# sandbox_main_v2e.net
KiCad netlist of a schematic drawn in EAGLE
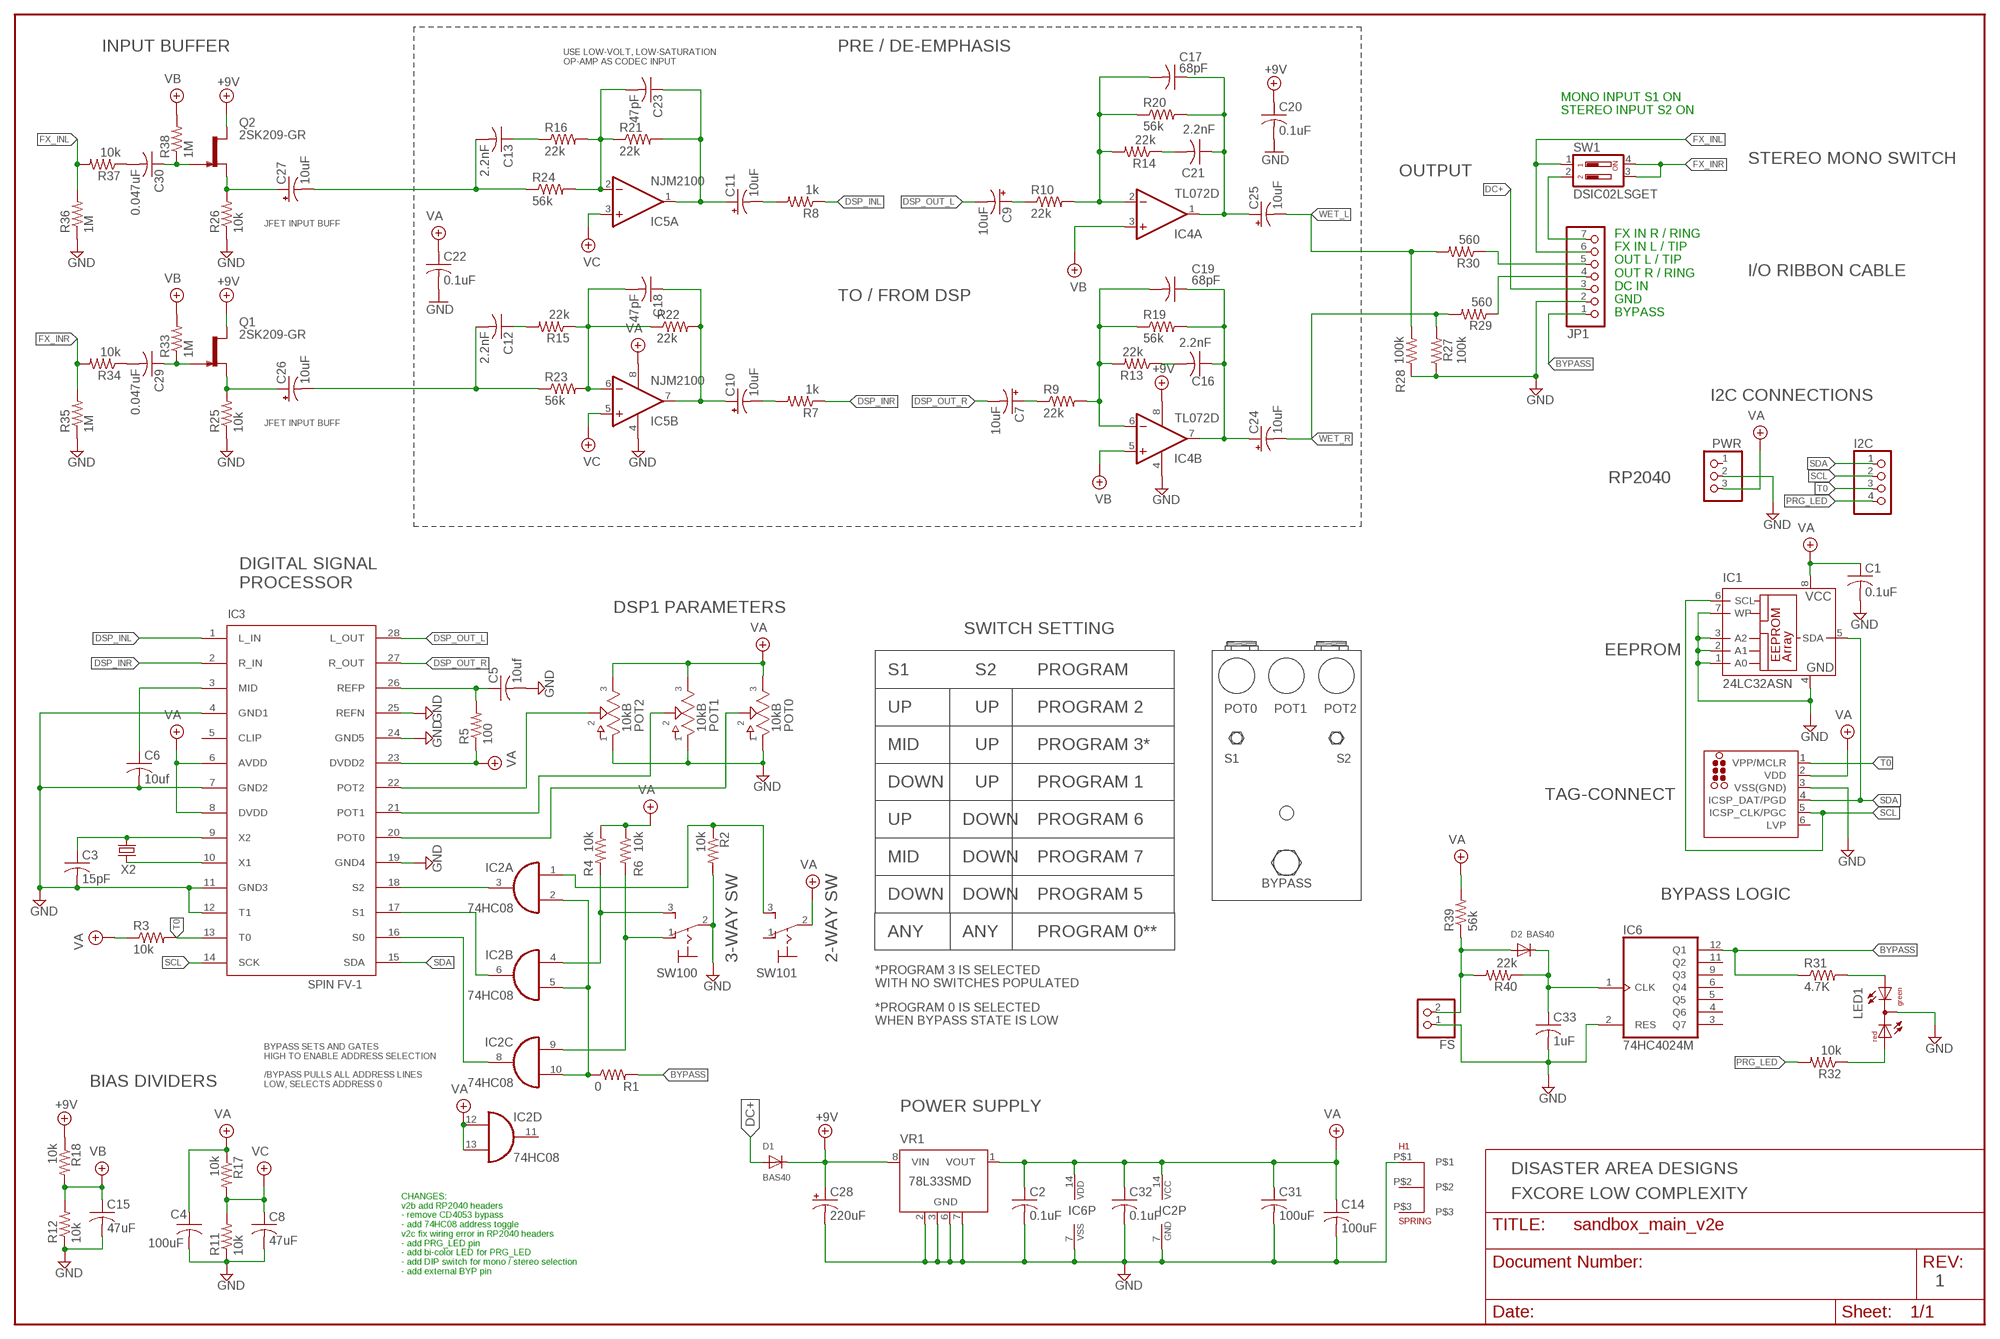
[diagram p0: schematic, sheet 1]

(export (version "E")
  (design (tool "Eeschema 10.0.6"))
  (components
    (comp (ref "C1")
      (value "0.1uF")
      (footprint "eagle-import:C0805K")
      (libsource (lib "eagle-import") (part "C-USC0805K"))
    )
    (comp (ref "C2")
      (value "0.1uF")
      (footprint "eagle-import:C0805K")
      (libsource (lib "eagle-import") (part "C-USC0805K"))
    )
    (comp (ref "C3")
      (value "15pF")
      (footprint "eagle-import:C0805K")
      (libsource (lib "eagle-import") (part "C-USC0805K"))
    )
    (comp (ref "C4")
      (value "100uF")
      (footprint "eagle-import:C1206K")
      (libsource (lib "eagle-import") (part "C-USC1206K"))
    )
    (comp (ref "C5")
      (value "10uf")
      (footprint "eagle-import:C0805K")
      (libsource (lib "eagle-import") (part "C-USC0805K"))
    )
    (comp (ref "C6")
      (value "10uf")
      (footprint "eagle-import:C0805K")
      (libsource (lib "eagle-import") (part "C-USC0805K"))
    )
    (comp (ref "C7")
      (value "10uF")
      (footprint "eagle-import:CT3216")
      (libsource (lib "eagle-import") (part "CPOL-USCT3216"))
    )
    (comp (ref "C8")
      (value "47uF")
      (footprint "eagle-import:C1206K")
      (libsource (lib "eagle-import") (part "C-USC1206K"))
    )
    (comp (ref "C9")
      (value "10uF")
      (footprint "eagle-import:CT3216")
      (libsource (lib "eagle-import") (part "CPOL-USCT3216"))
    )
    (comp (ref "C10")
      (value "10uF")
      (footprint "eagle-import:CT3216")
      (libsource (lib "eagle-import") (part "CPOL-USCT3216"))
    )
    (comp (ref "C11")
      (value "10uF")
      (footprint "eagle-import:CT3216")
      (libsource (lib "eagle-import") (part "CPOL-USCT3216"))
    )
    (comp (ref "C12")
      (value "2.2nF")
      (footprint "eagle-import:C0805K")
      (libsource (lib "eagle-import") (part "C-USC0805K"))
    )
    (comp (ref "C13")
      (value "2.2nF")
      (footprint "eagle-import:C0805K")
      (libsource (lib "eagle-import") (part "C-USC0805K"))
    )
    (comp (ref "C14")
      (value "100uF")
      (footprint "eagle-import:C1206K")
      (libsource (lib "eagle-import") (part "C-USC1206K"))
    )
    (comp (ref "C15")
      (value "47uF")
      (footprint "eagle-import:C1206K")
      (libsource (lib "eagle-import") (part "C-USC1206K"))
    )
    (comp (ref "C16")
      (value "2.2nF")
      (footprint "eagle-import:C0805K")
      (libsource (lib "eagle-import") (part "C-USC0805K"))
    )
    (comp (ref "C17")
      (value "68pF")
      (footprint "eagle-import:C0805K")
      (libsource (lib "eagle-import") (part "C-USC0805K"))
    )
    (comp (ref "C18")
      (value "47pF")
      (footprint "eagle-import:C0805K")
      (libsource (lib "eagle-import") (part "C-USC0805K"))
    )
    (comp (ref "C19")
      (value "68pF")
      (footprint "eagle-import:C0805K")
      (libsource (lib "eagle-import") (part "C-USC0805K"))
    )
    (comp (ref "C20")
      (value "0.1uF")
      (footprint "eagle-import:C0805K")
      (libsource (lib "eagle-import") (part "C-USC0805K"))
    )
    (comp (ref "C21")
      (value "2.2nF")
      (footprint "eagle-import:C0805K")
      (libsource (lib "eagle-import") (part "C-USC0805K"))
    )
    (comp (ref "C22")
      (value "0.1uF")
      (footprint "eagle-import:C0805K")
      (libsource (lib "eagle-import") (part "C-USC0805K"))
    )
    (comp (ref "C23")
      (value "47pF")
      (footprint "eagle-import:C0805K")
      (libsource (lib "eagle-import") (part "C-USC0805K"))
    )
    (comp (ref "C24")
      (value "10uF")
      (footprint "eagle-import:CT3216")
      (libsource (lib "eagle-import") (part "CPOL-USCT3216"))
    )
    (comp (ref "C25")
      (value "10uF")
      (footprint "eagle-import:CT3216")
      (libsource (lib "eagle-import") (part "CPOL-USCT3216"))
    )
    (comp (ref "C26")
      (value "10uF")
      (footprint "eagle-import:CT3216")
      (libsource (lib "eagle-import") (part "CPOL-USCT3216"))
    )
    (comp (ref "C27")
      (value "10uF")
      (footprint "eagle-import:CT3216")
      (libsource (lib "eagle-import") (part "CPOL-USCT3216"))
    )
    (comp (ref "C28")
      (value "220uF")
      (footprint "eagle-import:PANASONIC_D")
      (libsource (lib "eagle-import") (part "CPOL-USD"))
    )
    (comp (ref "C29")
      (value "0.047uF")
      (footprint "eagle-import:C1206K")
      (libsource (lib "eagle-import") (part "C-USC1206K"))
    )
    (comp (ref "C30")
      (value "0.047uF")
      (footprint "eagle-import:C1206K")
      (libsource (lib "eagle-import") (part "C-USC1206K"))
    )
    (comp (ref "C31")
      (value "100uF")
      (footprint "eagle-import:C1206K")
      (libsource (lib "eagle-import") (part "C-USC1206K"))
    )
    (comp (ref "C32")
      (value "0.1uF")
      (footprint "eagle-import:C0805K")
      (libsource (lib "eagle-import") (part "C-USC0805K"))
    )
    (comp (ref "C33")
      (value "1uF")
      (footprint "eagle-import:C0805K")
      (libsource (lib "eagle-import") (part "C-USC0805K"))
    )
    (comp (ref "D1")
      (value "BAS40")
      (footprint "eagle-import:SOT23-R")
      (libsource (lib "eagle-import") (part "DIODESOT23_REFLOW"))
    )
    (comp (ref "D2")
      (value "BAS40")
      (footprint "eagle-import:SOT23-R")
      (libsource (lib "eagle-import") (part "DIODESOT23_REFLOW"))
    )
    (comp (ref "FS")
      (value "PINHD-1X2")
      (footprint "eagle-import:1X02")
      (libsource (lib "eagle-import") (part "PINHD-1X2"))
    )
    (comp (ref "H1")
      (value "628")
      (footprint "eagle-import:628")
      (libsource (lib "eagle-import") (part "628"))
    )
    (comp (ref "I2C")
      (value "PINHD-1X4")
      (footprint "eagle-import:1X04")
      (libsource (lib "eagle-import") (part "PINHD-1X4"))
    )
    (comp (ref "IC1")
      (value "24LC32ASN")
      (footprint "eagle-import:SO-08")
      (fields (field (name "MF") "MICROCHIP") (field (name "MPN") "24LC32A/SN"))
      (libsource (lib "eagle-import") (part "24SNLC32A"))
    )
    (comp (ref "IC2")
      (value "74HC08")
      (footprint "eagle-import:SO14")
      (libsource (lib "eagle-import") (part "7408DAC"))
    )
    (comp (ref "IC3")
      (value "SPINFV-1")
      (footprint "eagle-import:SOIC-28")
      (libsource (lib "eagle-import") (part "SPINFV-1"))
    )
    (comp (ref "IC4")
      (value "TL072D")
      (footprint "eagle-import:SO08")
      (libsource (lib "eagle-import") (part "TL072D"))
    )
    (comp (ref "IC5")
      (value "NJM2100")
      (footprint "eagle-import:SO08")
      (libsource (lib "eagle-import") (part "TL072D"))
    )
    (comp (ref "IC6")
      (value "74HC4024M")
      (footprint "eagle-import:SO14")
      (libsource (lib "eagle-import") (part "4024D"))
    )
    (comp (ref "JP1")
      (value "PINHD-1X7")
      (footprint "eagle-import:1X07")
      (libsource (lib "eagle-import") (part "PINHD-1X7"))
    )
    (comp (ref "LED1")
      (value "DUOLED-RG-C")
      (footprint "eagle-import:DUOLED-C-5MM")
      (libsource (lib "eagle-import") (part "DUOLED-RG-C"))
    )
    (comp (ref "POT0")
      (value "10kB")
      (footprint "eagle-import:POT_9MM_PACK_SM")
      (libsource (lib "eagle-import") (part "POT_9MM_317-2080F_SM"))
    )
    (comp (ref "POT1")
      (value "10kB")
      (footprint "eagle-import:POT_9MM_PACK_SM")
      (libsource (lib "eagle-import") (part "POT_9MM_317-2080F_SM"))
    )
    (comp (ref "POT2")
      (value "10kB")
      (footprint "eagle-import:POT_9MM_PACK_SM")
      (libsource (lib "eagle-import") (part "POT_9MM_317-2080F_SM"))
    )
    (comp (ref "PWR")
      (value "PINHD-1X3")
      (footprint "eagle-import:1X03")
      (libsource (lib "eagle-import") (part "PINHD-1X3"))
    )
    (comp (ref "Q1")
      (value "2SK209-GR")
      (footprint "eagle-import:SOT-23")
      (libsource (lib "eagle-import") (part "2N5457SMT"))
    )
    (comp (ref "Q2")
      (value "2SK209-GR")
      (footprint "eagle-import:SOT-23")
      (libsource (lib "eagle-import") (part "2N5457SMT"))
    )
    (comp (ref "R1")
      (value "0")
      (footprint "eagle-import:R0805")
      (libsource (lib "eagle-import") (part "R-US_R0805"))
    )
    (comp (ref "R2")
      (value "10k")
      (footprint "eagle-import:R0805")
      (libsource (lib "eagle-import") (part "R-US_R0805"))
    )
    (comp (ref "R3")
      (value "10k")
      (footprint "eagle-import:R0805")
      (libsource (lib "eagle-import") (part "R-US_R0805"))
    )
    (comp (ref "R4")
      (value "10k")
      (footprint "eagle-import:R0805")
      (libsource (lib "eagle-import") (part "R-US_R0805"))
    )
    (comp (ref "R5")
      (value "100")
      (footprint "eagle-import:R0805")
      (libsource (lib "eagle-import") (part "R-US_R0805"))
    )
    (comp (ref "R6")
      (value "10k")
      (footprint "eagle-import:R0805")
      (libsource (lib "eagle-import") (part "R-US_R0805"))
    )
    (comp (ref "R7")
      (value "1k")
      (footprint "eagle-import:R0805")
      (libsource (lib "eagle-import") (part "R-US_R0805"))
    )
    (comp (ref "R8")
      (value "1k")
      (footprint "eagle-import:R0805")
      (libsource (lib "eagle-import") (part "R-US_R0805"))
    )
    (comp (ref "R9")
      (value "22k")
      (footprint "eagle-import:R0805")
      (libsource (lib "eagle-import") (part "R-US_R0805"))
    )
    (comp (ref "R10")
      (value "22k")
      (footprint "eagle-import:R0805")
      (libsource (lib "eagle-import") (part "R-US_R0805"))
    )
    (comp (ref "R11")
      (value "10k")
      (footprint "eagle-import:R0805")
      (libsource (lib "eagle-import") (part "R-US_R0805"))
    )
    (comp (ref "R12")
      (value "10k")
      (footprint "eagle-import:R0805")
      (libsource (lib "eagle-import") (part "R-US_R0805"))
    )
    (comp (ref "R13")
      (value "22k")
      (footprint "eagle-import:R0805")
      (libsource (lib "eagle-import") (part "R-US_R0805"))
    )
    (comp (ref "R14")
      (value "22k")
      (footprint "eagle-import:R0805")
      (libsource (lib "eagle-import") (part "R-US_R0805"))
    )
    (comp (ref "R15")
      (value "22k")
      (footprint "eagle-import:R0805")
      (libsource (lib "eagle-import") (part "R-US_R0805"))
    )
    (comp (ref "R16")
      (value "22k")
      (footprint "eagle-import:R0805")
      (libsource (lib "eagle-import") (part "R-US_R0805"))
    )
    (comp (ref "R17")
      (value "10k")
      (footprint "eagle-import:R0805")
      (libsource (lib "eagle-import") (part "R-US_R0805"))
    )
    (comp (ref "R18")
      (value "10k")
      (footprint "eagle-import:R0805")
      (libsource (lib "eagle-import") (part "R-US_R0805"))
    )
    (comp (ref "R19")
      (value "56k")
      (footprint "eagle-import:R0805")
      (libsource (lib "eagle-import") (part "R-US_R0805"))
    )
    (comp (ref "R20")
      (value "56k")
      (footprint "eagle-import:R0805")
      (libsource (lib "eagle-import") (part "R-US_R0805"))
    )
    (comp (ref "R21")
      (value "22k")
      (footprint "eagle-import:R0805")
      (libsource (lib "eagle-import") (part "R-US_R0805"))
    )
    (comp (ref "R22")
      (value "22k")
      (footprint "eagle-import:R0805")
      (libsource (lib "eagle-import") (part "R-US_R0805"))
    )
    (comp (ref "R23")
      (value "56k")
      (footprint "eagle-import:R0805")
      (libsource (lib "eagle-import") (part "R-US_R0805"))
    )
    (comp (ref "R24")
      (value "56k")
      (footprint "eagle-import:R0805")
      (libsource (lib "eagle-import") (part "R-US_R0805"))
    )
    (comp (ref "R25")
      (value "10k")
      (footprint "eagle-import:R0805")
      (libsource (lib "eagle-import") (part "R-US_R0805"))
    )
    (comp (ref "R26")
      (value "10k")
      (footprint "eagle-import:R0805")
      (libsource (lib "eagle-import") (part "R-US_R0805"))
    )
    (comp (ref "R27")
      (value "100k")
      (footprint "eagle-import:R0805")
      (libsource (lib "eagle-import") (part "R-US_R0805"))
    )
    (comp (ref "R28")
      (value "100k")
      (footprint "eagle-import:R0805")
      (libsource (lib "eagle-import") (part "R-US_R0805"))
    )
    (comp (ref "R29")
      (value "560")
      (footprint "eagle-import:R0805")
      (libsource (lib "eagle-import") (part "R-US_R0805"))
    )
    (comp (ref "R30")
      (value "560")
      (footprint "eagle-import:R0805")
      (libsource (lib "eagle-import") (part "R-US_R0805"))
    )
    (comp (ref "R31")
      (value "4.7K")
      (footprint "eagle-import:R0805")
      (libsource (lib "eagle-import") (part "R-US_R0805"))
    )
    (comp (ref "R32")
      (value "10k")
      (footprint "eagle-import:R0805")
      (libsource (lib "eagle-import") (part "R-US_R0805"))
    )
    (comp (ref "R33")
      (value "1M")
      (footprint "eagle-import:R0805")
      (libsource (lib "eagle-import") (part "R-US_R0805"))
    )
    (comp (ref "R34")
      (value "10k")
      (footprint "eagle-import:R0805")
      (libsource (lib "eagle-import") (part "R-US_R0805"))
    )
    (comp (ref "R35")
      (value "1M")
      (footprint "eagle-import:R0805")
      (libsource (lib "eagle-import") (part "R-US_R0805"))
    )
    (comp (ref "R36")
      (value "1M")
      (footprint "eagle-import:R0805")
      (libsource (lib "eagle-import") (part "R-US_R0805"))
    )
    (comp (ref "R37")
      (value "10k")
      (footprint "eagle-import:R0805")
      (libsource (lib "eagle-import") (part "R-US_R0805"))
    )
    (comp (ref "R38")
      (value "1M")
      (footprint "eagle-import:R0805")
      (libsource (lib "eagle-import") (part "R-US_R0805"))
    )
    (comp (ref "R39")
      (value "56k")
      (footprint "eagle-import:R0805")
      (libsource (lib "eagle-import") (part "R-US_R0805"))
    )
    (comp (ref "R40")
      (value "22k")
      (footprint "eagle-import:R0805")
      (libsource (lib "eagle-import") (part "R-US_R0805"))
    )
    (comp (ref "SW1")
      (value "DSIC02LSGET")
      (footprint "eagle-import:CTS-219-02")
      (libsource (lib "eagle-import") (part "219-02"))
    )
    (comp (ref "SW100")
      (value "320-916")
      (footprint "eagle-import:320-916")
      (libsource (lib "eagle-import") (part "320-916"))
    )
    (comp (ref "SW101")
      (value "320-916")
      (footprint "eagle-import:320-916")
      (libsource (lib "eagle-import") (part "320-916"))
    )
    (comp (ref "TC1")
      (value "TC2030_ICSP-MCP-NL")
      (footprint "eagle-import:TC2030-MCP-NL")
      (libsource (lib "eagle-import") (part "TC2030_ICSP-MCP-NL"))
    )
    (comp (ref "VR1")
      (value "78L33SMD")
      (footprint "eagle-import:SO08")
      (libsource (lib "eagle-import") (part "78LSMD05"))
    )
    (comp (ref "X2")
      (value "32.768kHz")
      (footprint "eagle-import:CRYSTAL-SMD-3.2X1.5MM")
      (libsource (lib "eagle-import") (part "CRYSTAL3.2X1.5MM"))
    )
  )
  (nets
    (net (code "1") (name "+9V") (class "Default")
      (node (ref "C20") (pin "1") (pinfunction "1_1") (pintype "passive"))
      (node (ref "C28") (pin "+") (pinfunction "+_+") (pintype "passive"))
      (node (ref "D1") (pin "3") (pinfunction "C_3") (pintype "passive"))
      (node (ref "IC4") (pin "8") (pinfunction "V+_8") (pintype "power_in"))
      (node (ref "Q1") (pin "2") (pinfunction "D_2") (pintype "passive"))
      (node (ref "Q2") (pin "2") (pinfunction "D_2") (pintype "passive"))
      (node (ref "R18") (pin "1") (pinfunction "1_1") (pintype "passive"))
      (node (ref "VR1") (pin "8") (pinfunction "VIN_8") (pintype "passive"))
    )
    (net (code "2") (name "BYPASS") (class "Default")
      (node (ref "IC6") (pin "12") (pinfunction "Q1_12") (pintype "output"))
      (node (ref "JP1") (pin "1") (pinfunction "1_1") (pintype "passive"))
      (node (ref "R1") (pin "2") (pinfunction "2_2") (pintype "passive"))
      (node (ref "R31") (pin "1") (pinfunction "1_1") (pintype "passive"))
    )
    (net (code "3") (name "DC+") (class "Default")
      (node (ref "D1") (pin "1") (pinfunction "A_1") (pintype "passive"))
      (node (ref "JP1") (pin "3") (pinfunction "3_3") (pintype "passive"))
    )
    (net (code "4") (name "DSP_INL") (class "Default")
      (node (ref "IC3") (pin "1") (pinfunction "L_IN_1") (pintype "bidirectional"))
      (node (ref "R8") (pin "1") (pinfunction "1_1") (pintype "passive"))
    )
    (net (code "5") (name "DSP_INR") (class "Default")
      (node (ref "IC3") (pin "2") (pinfunction "R_IN_2") (pintype "bidirectional"))
      (node (ref "R7") (pin "1") (pinfunction "1_1") (pintype "passive"))
    )
    (net (code "6") (name "DSP_OUT_L") (class "Default")
      (node (ref "C9") (pin "-") (pinfunction "-_-") (pintype "passive"))
      (node (ref "IC3") (pin "28") (pinfunction "L_OUT_28") (pintype "bidirectional"))
    )
    (net (code "7") (name "DSP_OUT_R") (class "Default")
      (node (ref "C7") (pin "-") (pinfunction "-_-") (pintype "passive"))
      (node (ref "IC3") (pin "27") (pinfunction "R_OUT_27") (pintype "bidirectional"))
    )
    (net (code "8") (name "FX_INL") (class "Default")
      (node (ref "JP1") (pin "6") (pinfunction "6_6") (pintype "passive"))
      (node (ref "R36") (pin "2") (pinfunction "2_2") (pintype "passive"))
      (node (ref "R37") (pin "2") (pinfunction "2_2") (pintype "passive"))
      (node (ref "SW1") (pin "1") (pinfunction "1_1") (pintype "passive"))
    )
    (net (code "9") (name "FX_INR") (class "Default")
      (node (ref "R34") (pin "2") (pinfunction "2_2") (pintype "passive"))
      (node (ref "R35") (pin "2") (pinfunction "2_2") (pintype "passive"))
      (node (ref "SW1") (pin "3") (pinfunction "3_3") (pintype "passive"))
      (node (ref "SW1") (pin "4") (pinfunction "4_4") (pintype "passive"))
    )
    (net (code "10") (name "GND") (class "Default")
      (node (ref "C1") (pin "2") (pinfunction "2_2") (pintype "passive"))
      (node (ref "C14") (pin "2") (pinfunction "2_2") (pintype "passive"))
      (node (ref "C15") (pin "2") (pinfunction "2_2") (pintype "passive"))
      (node (ref "C2") (pin "2") (pinfunction "2_2") (pintype "passive"))
      (node (ref "C20") (pin "2") (pinfunction "2_2") (pintype "passive"))
      (node (ref "C22") (pin "2") (pinfunction "2_2") (pintype "passive"))
      (node (ref "C28") (pin "-") (pinfunction "-_-") (pintype "passive"))
      (node (ref "C3") (pin "2") (pinfunction "2_2") (pintype "passive"))
      (node (ref "C31") (pin "2") (pinfunction "2_2") (pintype "passive"))
      (node (ref "C32") (pin "2") (pinfunction "2_2") (pintype "passive"))
      (node (ref "C33") (pin "2") (pinfunction "2_2") (pintype "passive"))
      (node (ref "C4") (pin "2") (pinfunction "2_2") (pintype "passive"))
      (node (ref "C5") (pin "2") (pinfunction "2_2") (pintype "passive"))
      (node (ref "C6") (pin "2") (pinfunction "2_2") (pintype "passive"))
      (node (ref "C8") (pin "2") (pinfunction "2_2") (pintype "passive"))
      (node (ref "FS") (pin "1") (pinfunction "1_1") (pintype "passive"))
      (node (ref "H1") (pin "P$1") (pinfunction "P$1_P$1") (pintype "bidirectional"))
      (node (ref "IC1") (pin "1") (pinfunction "A0_1") (pintype "input"))
      (node (ref "IC1") (pin "2") (pinfunction "A1_2") (pintype "input"))
      (node (ref "IC1") (pin "3") (pinfunction "A2_3") (pintype "input"))
      (node (ref "IC1") (pin "4") (pinfunction "GND_4") (pintype "power_in"))
      (node (ref "IC1") (pin "7") (pinfunction "WP_7") (pintype "input"))
      (node (ref "IC2") (pin "7") (pinfunction "GND_7") (pintype "power_in"))
      (node (ref "IC3") (pin "11") (pinfunction "GND3_11") (pintype "bidirectional"))
      (node (ref "IC3") (pin "12") (pinfunction "T1_12") (pintype "bidirectional"))
      (node (ref "IC3") (pin "19") (pinfunction "GND4_19") (pintype "bidirectional"))
      (node (ref "IC3") (pin "24") (pinfunction "GND5_24") (pintype "bidirectional"))
      (node (ref "IC3") (pin "25") (pinfunction "REFN_25") (pintype "bidirectional"))
      (node (ref "IC3") (pin "4") (pinfunction "GND1_4") (pintype "bidirectional"))
      (node (ref "IC3") (pin "7") (pinfunction "GND2_7") (pintype "bidirectional"))
      (node (ref "IC4") (pin "4") (pinfunction "V-_4") (pintype "power_in"))
      (node (ref "IC5") (pin "4") (pinfunction "V-_4") (pintype "power_in"))
      (node (ref "IC6") (pin "2") (pinfunction "RES_2") (pintype "input"))
      (node (ref "IC6") (pin "7") (pinfunction "VSS_7") (pintype "power_in"))
      (node (ref "JP1") (pin "2") (pinfunction "2_2") (pintype "passive"))
      (node (ref "LED1") (pin "C") (pinfunction "C_C") (pintype "passive"))
      (node (ref "POT0") (pin "P$1") (pinfunction "P$1_P$1") (pintype "bidirectional"))
      (node (ref "POT1") (pin "P$1") (pinfunction "P$1_P$1") (pintype "bidirectional"))
      (node (ref "POT2") (pin "P$1") (pinfunction "P$1_P$1") (pintype "bidirectional"))
      (node (ref "PWR") (pin "2") (pinfunction "2_2") (pintype "passive"))
      (node (ref "R11") (pin "1") (pinfunction "1_1") (pintype "passive"))
      (node (ref "R12") (pin "1") (pinfunction "1_1") (pintype "passive"))
      (node (ref "R2") (pin "2") (pinfunction "2_2") (pintype "passive"))
      (node (ref "R25") (pin "1") (pinfunction "1_1") (pintype "passive"))
      (node (ref "R26") (pin "1") (pinfunction "1_1") (pintype "passive"))
      (node (ref "R27") (pin "1") (pinfunction "1_1") (pintype "passive"))
      (node (ref "R28") (pin "1") (pinfunction "1_1") (pintype "passive"))
      (node (ref "R35") (pin "1") (pinfunction "1_1") (pintype "passive"))
      (node (ref "R36") (pin "1") (pinfunction "1_1") (pintype "passive"))
      (node (ref "SW100") (pin "2") (pinfunction "P_2") (pintype "passive"))
      (node (ref "TC1") (pin "3") (pinfunction "VSS(GND)_3") (pintype "power_in"))
      (node (ref "VR1") (pin "2") (pinfunction "GND_2") (pintype "power_in"))
      (node (ref "VR1") (pin "3") (pinfunction "GND_3") (pintype "power_in"))
      (node (ref "VR1") (pin "6") (pinfunction "GND_6") (pintype "power_in"))
      (node (ref "VR1") (pin "7") (pinfunction "GND_7") (pintype "power_in"))
    )
    (net (code "11") (name "Net-(C7-Pad+)") (class "Default")
      (node (ref "C7") (pin "+") (pinfunction "+_+") (pintype "passive"))
      (node (ref "R9") (pin "1") (pinfunction "1_1") (pintype "passive"))
    )
    (net (code "12") (name "Net-(C9-Pad+)") (class "Default")
      (node (ref "C9") (pin "+") (pinfunction "+_+") (pintype "passive"))
      (node (ref "R10") (pin "1") (pinfunction "1_1") (pintype "passive"))
    )
    (net (code "13") (name "Net-(C10-Pad-)") (class "Default")
      (node (ref "C10") (pin "-") (pinfunction "-_-") (pintype "passive"))
      (node (ref "R7") (pin "2") (pinfunction "2_2") (pintype "passive"))
    )
    (net (code "14") (name "Net-(C11-Pad-)") (class "Default")
      (node (ref "C11") (pin "-") (pinfunction "-_-") (pintype "passive"))
      (node (ref "R8") (pin "2") (pinfunction "2_2") (pintype "passive"))
    )
    (net (code "15") (name "Net-(C12-Pad1)") (class "Default")
      (node (ref "C12") (pin "1") (pinfunction "1_1") (pintype "passive"))
      (node (ref "R15") (pin "2") (pinfunction "2_2") (pintype "passive"))
    )
    (net (code "16") (name "Net-(C12-Pad2)") (class "Default")
      (node (ref "C12") (pin "2") (pinfunction "2_2") (pintype "passive"))
      (node (ref "C26") (pin "-") (pinfunction "-_-") (pintype "passive"))
      (node (ref "R23") (pin "1") (pinfunction "1_1") (pintype "passive"))
    )
    (net (code "17") (name "Net-(C13-Pad1)") (class "Default")
      (node (ref "C13") (pin "1") (pinfunction "1_1") (pintype "passive"))
      (node (ref "R16") (pin "1") (pinfunction "1_1") (pintype "passive"))
    )
    (net (code "18") (name "Net-(C13-Pad2)") (class "Default")
      (node (ref "C13") (pin "2") (pinfunction "2_2") (pintype "passive"))
      (node (ref "C27") (pin "-") (pinfunction "-_-") (pintype "passive"))
      (node (ref "R24") (pin "1") (pinfunction "1_1") (pintype "passive"))
    )
    (net (code "19") (name "Net-(C16-Pad2)") (class "Default")
      (node (ref "C16") (pin "2") (pinfunction "2_2") (pintype "passive"))
      (node (ref "R13") (pin "1") (pinfunction "1_1") (pintype "passive"))
    )
    (net (code "20") (name "Net-(C21-Pad2)") (class "Default")
      (node (ref "C21") (pin "2") (pinfunction "2_2") (pintype "passive"))
      (node (ref "R14") (pin "1") (pinfunction "1_1") (pintype "passive"))
    )
    (net (code "21") (name "Net-(C29-Pad2)") (class "Default")
      (node (ref "C29") (pin "2") (pinfunction "2_2") (pintype "passive"))
      (node (ref "R34") (pin "1") (pinfunction "1_1") (pintype "passive"))
    )
    (net (code "22") (name "Net-(C30-Pad2)") (class "Default")
      (node (ref "C30") (pin "2") (pinfunction "2_2") (pintype "passive"))
      (node (ref "R37") (pin "1") (pinfunction "1_1") (pintype "passive"))
    )
    (net (code "23") (name "Net-(D2-A)") (class "Default")
      (node (ref "D2") (pin "1") (pinfunction "A_1") (pintype "passive"))
      (node (ref "FS") (pin "2") (pinfunction "2_2") (pintype "passive"))
      (node (ref "R39") (pin "1") (pinfunction "1_1") (pintype "passive"))
      (node (ref "R40") (pin "2") (pinfunction "2_2") (pintype "passive"))
    )
    (net (code "24") (name "Net-(D2-C)") (class "Default")
      (node (ref "C33") (pin "1") (pinfunction "1_1") (pintype "passive"))
      (node (ref "D2") (pin "3") (pinfunction "C_3") (pintype "passive"))
      (node (ref "IC6") (pin "1") (pinfunction "CLK_1") (pintype "input"))
      (node (ref "R40") (pin "1") (pinfunction "1_1") (pintype "passive"))
    )
    (net (code "25") (name "Net-(IC2A-I0)") (class "Default")
      (node (ref "IC2") (pin "1") (pinfunction "I0_1") (pintype "input"))
      (node (ref "R2") (pin "1") (pinfunction "1_1") (pintype "passive"))
      (node (ref "SW101") (pin "3") (pinfunction "S_3") (pintype "passive"))
    )
    (net (code "26") (name "Net-(IC2A-I1)") (class "Default")
      (node (ref "IC2") (pin "10") (pinfunction "I1_10") (pintype "input"))
      (node (ref "IC2") (pin "2") (pinfunction "I1_2") (pintype "input"))
      (node (ref "IC2") (pin "5") (pinfunction "I1_5") (pintype "input"))
      (node (ref "R1") (pin "1") (pinfunction "1_1") (pintype "passive"))
    )
    (net (code "27") (name "Net-(IC2A-O)") (class "Default")
      (node (ref "IC2") (pin "3") (pinfunction "O_3") (pintype "output"))
      (node (ref "IC3") (pin "18") (pinfunction "S2_18") (pintype "bidirectional"))
    )
    (net (code "28") (name "Net-(IC2B-I0)") (class "Default")
      (node (ref "IC2") (pin "4") (pinfunction "I0_4") (pintype "input"))
      (node (ref "R4") (pin "2") (pinfunction "2_2") (pintype "passive"))
      (node (ref "SW100") (pin "3") (pinfunction "S_3") (pintype "passive"))
    )
    (net (code "29") (name "Net-(IC2B-O)") (class "Default")
      (node (ref "IC2") (pin "6") (pinfunction "O_6") (pintype "output"))
      (node (ref "IC3") (pin "17") (pinfunction "S1_17") (pintype "bidirectional"))
    )
    (net (code "30") (name "Net-(IC2C-I0)") (class "Default")
      (node (ref "IC2") (pin "9") (pinfunction "I0_9") (pintype "input"))
      (node (ref "R6") (pin "2") (pinfunction "2_2") (pintype "passive"))
      (node (ref "SW100") (pin "1") (pinfunction "O_1") (pintype "passive"))
    )
    (net (code "31") (name "Net-(IC2C-O)") (class "Default")
      (node (ref "IC2") (pin "8") (pinfunction "O_8") (pintype "output"))
      (node (ref "IC3") (pin "16") (pinfunction "S0_16") (pintype "bidirectional"))
    )
    (net (code "32") (name "Net-(IC3-MID)") (class "Default")
      (node (ref "C6") (pin "1") (pinfunction "1_1") (pintype "passive"))
      (node (ref "IC3") (pin "3") (pinfunction "MID_3") (pintype "bidirectional"))
    )
    (net (code "33") (name "Net-(IC3-POT0)") (class "Default")
      (node (ref "IC3") (pin "20") (pinfunction "POT0_20") (pintype "bidirectional"))
      (node (ref "POT0") (pin "P$2") (pinfunction "P$2_P$2") (pintype "bidirectional"))
    )
    (net (code "34") (name "Net-(IC3-POT1)") (class "Default")
      (node (ref "IC3") (pin "21") (pinfunction "POT1_21") (pintype "bidirectional"))
      (node (ref "POT1") (pin "P$2") (pinfunction "P$2_P$2") (pintype "bidirectional"))
    )
    (net (code "35") (name "Net-(IC3-POT2)") (class "Default")
      (node (ref "IC3") (pin "22") (pinfunction "POT2_22") (pintype "bidirectional"))
      (node (ref "POT2") (pin "P$2") (pinfunction "P$2_P$2") (pintype "bidirectional"))
    )
    (net (code "36") (name "Net-(IC3-REFP)") (class "Default")
      (node (ref "C5") (pin "1") (pinfunction "1_1") (pintype "passive"))
      (node (ref "IC3") (pin "26") (pinfunction "REFP_26") (pintype "bidirectional"))
      (node (ref "R5") (pin "2") (pinfunction "2_2") (pintype "passive"))
    )
    (net (code "37") (name "Net-(IC3-X1)") (class "Default")
      (node (ref "IC3") (pin "10") (pinfunction "X1_10") (pintype "bidirectional"))
      (node (ref "X2") (pin "P$1") (pinfunction "1_P$1") (pintype "passive"))
    )
    (net (code "38") (name "Net-(IC3-X2)") (class "Default")
      (node (ref "C3") (pin "1") (pinfunction "1_1") (pintype "passive"))
      (node (ref "IC3") (pin "9") (pinfunction "X2_9") (pintype "bidirectional"))
      (node (ref "X2") (pin "P$2") (pinfunction "2_P$2") (pintype "passive"))
    )
    (net (code "39") (name "Net-(IC4A--IN)") (class "Default")
      (node (ref "C17") (pin "2") (pinfunction "2_2") (pintype "passive"))
      (node (ref "IC4") (pin "2") (pinfunction "-IN_2") (pintype "input"))
      (node (ref "R10") (pin "2") (pinfunction "2_2") (pintype "passive"))
      (node (ref "R14") (pin "2") (pinfunction "2_2") (pintype "passive"))
      (node (ref "R20") (pin "1") (pinfunction "1_1") (pintype "passive"))
    )
    (net (code "40") (name "Net-(IC4A-OUT)") (class "Default")
      (node (ref "C17") (pin "1") (pinfunction "1_1") (pintype "passive"))
      (node (ref "C21") (pin "1") (pinfunction "1_1") (pintype "passive"))
      (node (ref "C25") (pin "+") (pinfunction "+_+") (pintype "passive"))
      (node (ref "IC4") (pin "1") (pinfunction "OUT_1") (pintype "output"))
      (node (ref "R20") (pin "2") (pinfunction "2_2") (pintype "passive"))
    )
    (net (code "41") (name "Net-(IC4B--IN)") (class "Default")
      (node (ref "C19") (pin "2") (pinfunction "2_2") (pintype "passive"))
      (node (ref "IC4") (pin "6") (pinfunction "-IN_6") (pintype "input"))
      (node (ref "R13") (pin "2") (pinfunction "2_2") (pintype "passive"))
      (node (ref "R19") (pin "1") (pinfunction "1_1") (pintype "passive"))
      (node (ref "R9") (pin "2") (pinfunction "2_2") (pintype "passive"))
    )
    (net (code "42") (name "Net-(IC4B-OUT)") (class "Default")
      (node (ref "C16") (pin "1") (pinfunction "1_1") (pintype "passive"))
      (node (ref "C19") (pin "1") (pinfunction "1_1") (pintype "passive"))
      (node (ref "C24") (pin "+") (pinfunction "+_+") (pintype "passive"))
      (node (ref "IC4") (pin "7") (pinfunction "OUT_7") (pintype "output"))
      (node (ref "R19") (pin "2") (pinfunction "2_2") (pintype "passive"))
    )
    (net (code "43") (name "Net-(IC5A--IN)") (class "Default")
      (node (ref "C23") (pin "2") (pinfunction "2_2") (pintype "passive"))
      (node (ref "IC5") (pin "2") (pinfunction "-IN_2") (pintype "input"))
      (node (ref "R16") (pin "2") (pinfunction "2_2") (pintype "passive"))
      (node (ref "R21") (pin "1") (pinfunction "1_1") (pintype "passive"))
      (node (ref "R24") (pin "2") (pinfunction "2_2") (pintype "passive"))
    )
    (net (code "44") (name "Net-(IC5A-OUT)") (class "Default")
      (node (ref "C11") (pin "+") (pinfunction "+_+") (pintype "passive"))
      (node (ref "C23") (pin "1") (pinfunction "1_1") (pintype "passive"))
      (node (ref "IC5") (pin "1") (pinfunction "OUT_1") (pintype "output"))
      (node (ref "R21") (pin "2") (pinfunction "2_2") (pintype "passive"))
    )
    (net (code "45") (name "Net-(IC5B--IN)") (class "Default")
      (node (ref "C18") (pin "2") (pinfunction "2_2") (pintype "passive"))
      (node (ref "IC5") (pin "6") (pinfunction "-IN_6") (pintype "input"))
      (node (ref "R15") (pin "1") (pinfunction "1_1") (pintype "passive"))
      (node (ref "R22") (pin "1") (pinfunction "1_1") (pintype "passive"))
      (node (ref "R23") (pin "2") (pinfunction "2_2") (pintype "passive"))
    )
    (net (code "46") (name "Net-(IC5B-OUT)") (class "Default")
      (node (ref "C10") (pin "+") (pinfunction "+_+") (pintype "passive"))
      (node (ref "C18") (pin "1") (pinfunction "1_1") (pintype "passive"))
      (node (ref "IC5") (pin "7") (pinfunction "OUT_7") (pintype "output"))
      (node (ref "R22") (pin "2") (pinfunction "2_2") (pintype "passive"))
    )
    (net (code "47") (name "Net-(JP1-Pad4)") (class "Default")
      (node (ref "JP1") (pin "4") (pinfunction "4_4") (pintype "passive"))
      (node (ref "R29") (pin "1") (pinfunction "1_1") (pintype "passive"))
    )
    (net (code "48") (name "Net-(JP1-Pad5)") (class "Default")
      (node (ref "JP1") (pin "5") (pinfunction "5_5") (pintype "passive"))
      (node (ref "R30") (pin "1") (pinfunction "1_1") (pintype "passive"))
    )
    (net (code "49") (name "Net-(JP1-Pad7)") (class "Default")
      (node (ref "JP1") (pin "7") (pinfunction "7_7") (pintype "passive"))
      (node (ref "SW1") (pin "2") (pinfunction "2_2") (pintype "passive"))
    )
    (net (code "50") (name "Net-(LED1-AG)") (class "Default")
      (node (ref "LED1") (pin "AX") (pinfunction "AG_AX") (pintype "passive"))
      (node (ref "R31") (pin "2") (pinfunction "2_2") (pintype "passive"))
    )
    (net (code "51") (name "Net-(LED1-PadAR)") (class "Default")
      (node (ref "LED1") (pin "AR") (pinfunction "AR_AR") (pintype "passive"))
      (node (ref "R32") (pin "1") (pinfunction "1_1") (pintype "passive"))
    )
    (net (code "52") (name "Net-(Q1-G)") (class "Default")
      (node (ref "C29") (pin "1") (pinfunction "1_1") (pintype "passive"))
      (node (ref "Q1") (pin "3") (pinfunction "G_3") (pintype "passive"))
      (node (ref "R33") (pin "1") (pinfunction "1_1") (pintype "passive"))
    )
    (net (code "53") (name "Net-(Q1-S)") (class "Default")
      (node (ref "C26") (pin "+") (pinfunction "+_+") (pintype "passive"))
      (node (ref "Q1") (pin "1") (pinfunction "S_1") (pintype "passive"))
      (node (ref "R25") (pin "2") (pinfunction "2_2") (pintype "passive"))
    )
    (net (code "54") (name "Net-(Q2-G)") (class "Default")
      (node (ref "C30") (pin "1") (pinfunction "1_1") (pintype "passive"))
      (node (ref "Q2") (pin "3") (pinfunction "G_3") (pintype "passive"))
      (node (ref "R38") (pin "1") (pinfunction "1_1") (pintype "passive"))
    )
    (net (code "55") (name "Net-(Q2-S)") (class "Default")
      (node (ref "C27") (pin "+") (pinfunction "+_+") (pintype "passive"))
      (node (ref "Q2") (pin "1") (pinfunction "S_1") (pintype "passive"))
      (node (ref "R26") (pin "2") (pinfunction "2_2") (pintype "passive"))
    )
    (net (code "56") (name "PRG_LED") (class "Default")
      (node (ref "I2C") (pin "4") (pinfunction "4_4") (pintype "passive"))
      (node (ref "R32") (pin "2") (pinfunction "2_2") (pintype "passive"))
    )
    (net (code "57") (name "SCL") (class "Default")
      (node (ref "I2C") (pin "2") (pinfunction "2_2") (pintype "passive"))
      (node (ref "IC1") (pin "6") (pinfunction "SCL_6") (pintype "input"))
      (node (ref "IC3") (pin "14") (pinfunction "SCK_14") (pintype "bidirectional"))
      (node (ref "TC1") (pin "5") (pinfunction "ICSP_CLK/PGC_5") (pintype "output"))
    )
    (net (code "58") (name "SDA") (class "Default")
      (node (ref "I2C") (pin "1") (pinfunction "1_1") (pintype "passive"))
      (node (ref "IC1") (pin "5") (pinfunction "SDA_5") (pintype "bidirectional"))
      (node (ref "IC3") (pin "15") (pinfunction "SDA_15") (pintype "bidirectional"))
      (node (ref "TC1") (pin "4") (pinfunction "ICSP_DAT/PGD_4") (pintype "bidirectional"))
    )
    (net (code "59") (name "T0") (class "Default")
      (node (ref "I2C") (pin "3") (pinfunction "3_3") (pintype "passive"))
      (node (ref "IC3") (pin "13") (pinfunction "T0_13") (pintype "bidirectional"))
      (node (ref "R3") (pin "2") (pinfunction "2_2") (pintype "passive"))
      (node (ref "TC1") (pin "1") (pinfunction "VPP/MCLR_1") (pintype "passive"))
    )
    (net (code "60") (name "VA") (class "Default")
      (node (ref "C1") (pin "1") (pinfunction "1_1") (pintype "passive"))
      (node (ref "C14") (pin "1") (pinfunction "1_1") (pintype "passive"))
      (node (ref "C2") (pin "1") (pinfunction "1_1") (pintype "passive"))
      (node (ref "C22") (pin "1") (pinfunction "1_1") (pintype "passive"))
      (node (ref "C31") (pin "1") (pinfunction "1_1") (pintype "passive"))
      (node (ref "C32") (pin "1") (pinfunction "1_1") (pintype "passive"))
      (node (ref "C4") (pin "1") (pinfunction "1_1") (pintype "passive"))
      (node (ref "IC1") (pin "8") (pinfunction "VCC_8") (pintype "power_in"))
      (node (ref "IC2") (pin "12") (pinfunction "I0_12") (pintype "input"))
      (node (ref "IC2") (pin "13") (pinfunction "I1_13") (pintype "input"))
      (node (ref "IC2") (pin "14") (pinfunction "VCC_14") (pintype "power_in"))
      (node (ref "IC3") (pin "23") (pinfunction "DVDD2_23") (pintype "bidirectional"))
      (node (ref "IC3") (pin "6") (pinfunction "AVDD_6") (pintype "bidirectional"))
      (node (ref "IC3") (pin "8") (pinfunction "DVDD_8") (pintype "bidirectional"))
      (node (ref "IC5") (pin "8") (pinfunction "V+_8") (pintype "power_in"))
      (node (ref "IC6") (pin "14") (pinfunction "VDD_14") (pintype "power_in"))
      (node (ref "POT0") (pin "P$3") (pinfunction "P$3_P$3") (pintype "bidirectional"))
      (node (ref "POT1") (pin "P$3") (pinfunction "P$3_P$3") (pintype "bidirectional"))
      (node (ref "POT2") (pin "P$3") (pinfunction "P$3_P$3") (pintype "bidirectional"))
      (node (ref "PWR") (pin "3") (pinfunction "3_3") (pintype "passive"))
      (node (ref "R17") (pin "1") (pinfunction "1_1") (pintype "passive"))
      (node (ref "R3") (pin "1") (pinfunction "1_1") (pintype "passive"))
      (node (ref "R39") (pin "2") (pinfunction "2_2") (pintype "passive"))
      (node (ref "R4") (pin "1") (pinfunction "1_1") (pintype "passive"))
      (node (ref "R5") (pin "1") (pinfunction "1_1") (pintype "passive"))
      (node (ref "R6") (pin "1") (pinfunction "1_1") (pintype "passive"))
      (node (ref "SW101") (pin "2") (pinfunction "P_2") (pintype "passive"))
      (node (ref "TC1") (pin "2") (pinfunction "VDD_2") (pintype "power_in"))
      (node (ref "VR1") (pin "1") (pinfunction "VOUT_1") (pintype "output"))
    )
    (net (code "61") (name "VB") (class "Default")
      (node (ref "C15") (pin "1") (pinfunction "1_1") (pintype "passive"))
      (node (ref "IC4") (pin "3") (pinfunction "+IN_3") (pintype "input"))
      (node (ref "IC4") (pin "5") (pinfunction "+IN_5") (pintype "input"))
      (node (ref "R12") (pin "2") (pinfunction "2_2") (pintype "passive"))
      (node (ref "R18") (pin "2") (pinfunction "2_2") (pintype "passive"))
      (node (ref "R33") (pin "2") (pinfunction "2_2") (pintype "passive"))
      (node (ref "R38") (pin "2") (pinfunction "2_2") (pintype "passive"))
    )
    (net (code "62") (name "VC") (class "Default")
      (node (ref "C8") (pin "1") (pinfunction "1_1") (pintype "passive"))
      (node (ref "IC5") (pin "3") (pinfunction "+IN_3") (pintype "input"))
      (node (ref "IC5") (pin "5") (pinfunction "+IN_5") (pintype "input"))
      (node (ref "R11") (pin "2") (pinfunction "2_2") (pintype "passive"))
      (node (ref "R17") (pin "2") (pinfunction "2_2") (pintype "passive"))
    )
    (net (code "63") (name "WET_L") (class "Default")
      (node (ref "C25") (pin "-") (pinfunction "-_-") (pintype "passive"))
      (node (ref "R28") (pin "2") (pinfunction "2_2") (pintype "passive"))
      (node (ref "R30") (pin "2") (pinfunction "2_2") (pintype "passive"))
    )
    (net (code "64") (name "WET_R") (class "Default")
      (node (ref "C24") (pin "-") (pinfunction "-_-") (pintype "passive"))
      (node (ref "R27") (pin "2") (pinfunction "2_2") (pintype "passive"))
      (node (ref "R29") (pin "2") (pinfunction "2_2") (pintype "passive"))
    )
    (net (code "65") (name "unconnected-(H1-PadP$2)") (class "Default")
      (node (ref "H1") (pin "P$2") (pinfunction "P$2_P$2") (pintype "bidirectional"))
    )
    (net (code "66") (name "unconnected-(H1-PadP$3)") (class "Default")
      (node (ref "H1") (pin "P$3") (pinfunction "P$3_P$3") (pintype "bidirectional"))
    )
    (net (code "67") (name "unconnected-(IC2D-O-Pad11)") (class "Default")
      (node (ref "IC2") (pin "11") (pinfunction "O_11") (pintype "output"))
    )
    (net (code "68") (name "unconnected-(IC3-CLIP-Pad5)") (class "Default")
      (node (ref "IC3") (pin "5") (pinfunction "CLIP_5") (pintype "bidirectional"))
    )
    (net (code "69") (name "unconnected-(IC6A-Q2-Pad11)") (class "Default")
      (node (ref "IC6") (pin "11") (pinfunction "Q2_11") (pintype "output"))
    )
    (net (code "70") (name "unconnected-(IC6A-Q3-Pad9)") (class "Default")
      (node (ref "IC6") (pin "9") (pinfunction "Q3_9") (pintype "output"))
    )
    (net (code "71") (name "unconnected-(IC6A-Q4-Pad6)") (class "Default")
      (node (ref "IC6") (pin "6") (pinfunction "Q4_6") (pintype "output"))
    )
    (net (code "72") (name "unconnected-(IC6A-Q5-Pad5)") (class "Default")
      (node (ref "IC6") (pin "5") (pinfunction "Q5_5") (pintype "output"))
    )
    (net (code "73") (name "unconnected-(IC6A-Q6-Pad4)") (class "Default")
      (node (ref "IC6") (pin "4") (pinfunction "Q6_4") (pintype "output"))
    )
    (net (code "74") (name "unconnected-(IC6A-Q7-Pad3)") (class "Default")
      (node (ref "IC6") (pin "3") (pinfunction "Q7_3") (pintype "output"))
    )
    (net (code "75") (name "unconnected-(PWR-Pad1)") (class "Default")
      (node (ref "PWR") (pin "1") (pinfunction "1_1") (pintype "passive"))
    )
    (net (code "76") (name "unconnected-(SW101-O-Pad1)") (class "Default")
      (node (ref "SW101") (pin "1") (pinfunction "O_1") (pintype "passive"))
    )
    (net (code "77") (name "unconnected-(TC1-LVP-Pad6)") (class "Default")
      (node (ref "TC1") (pin "6") (pinfunction "LVP_6") (pintype "bidirectional"))
    )
  )
)
